# design.net
KiCad netlist of a schematic drawn in Altium Designer
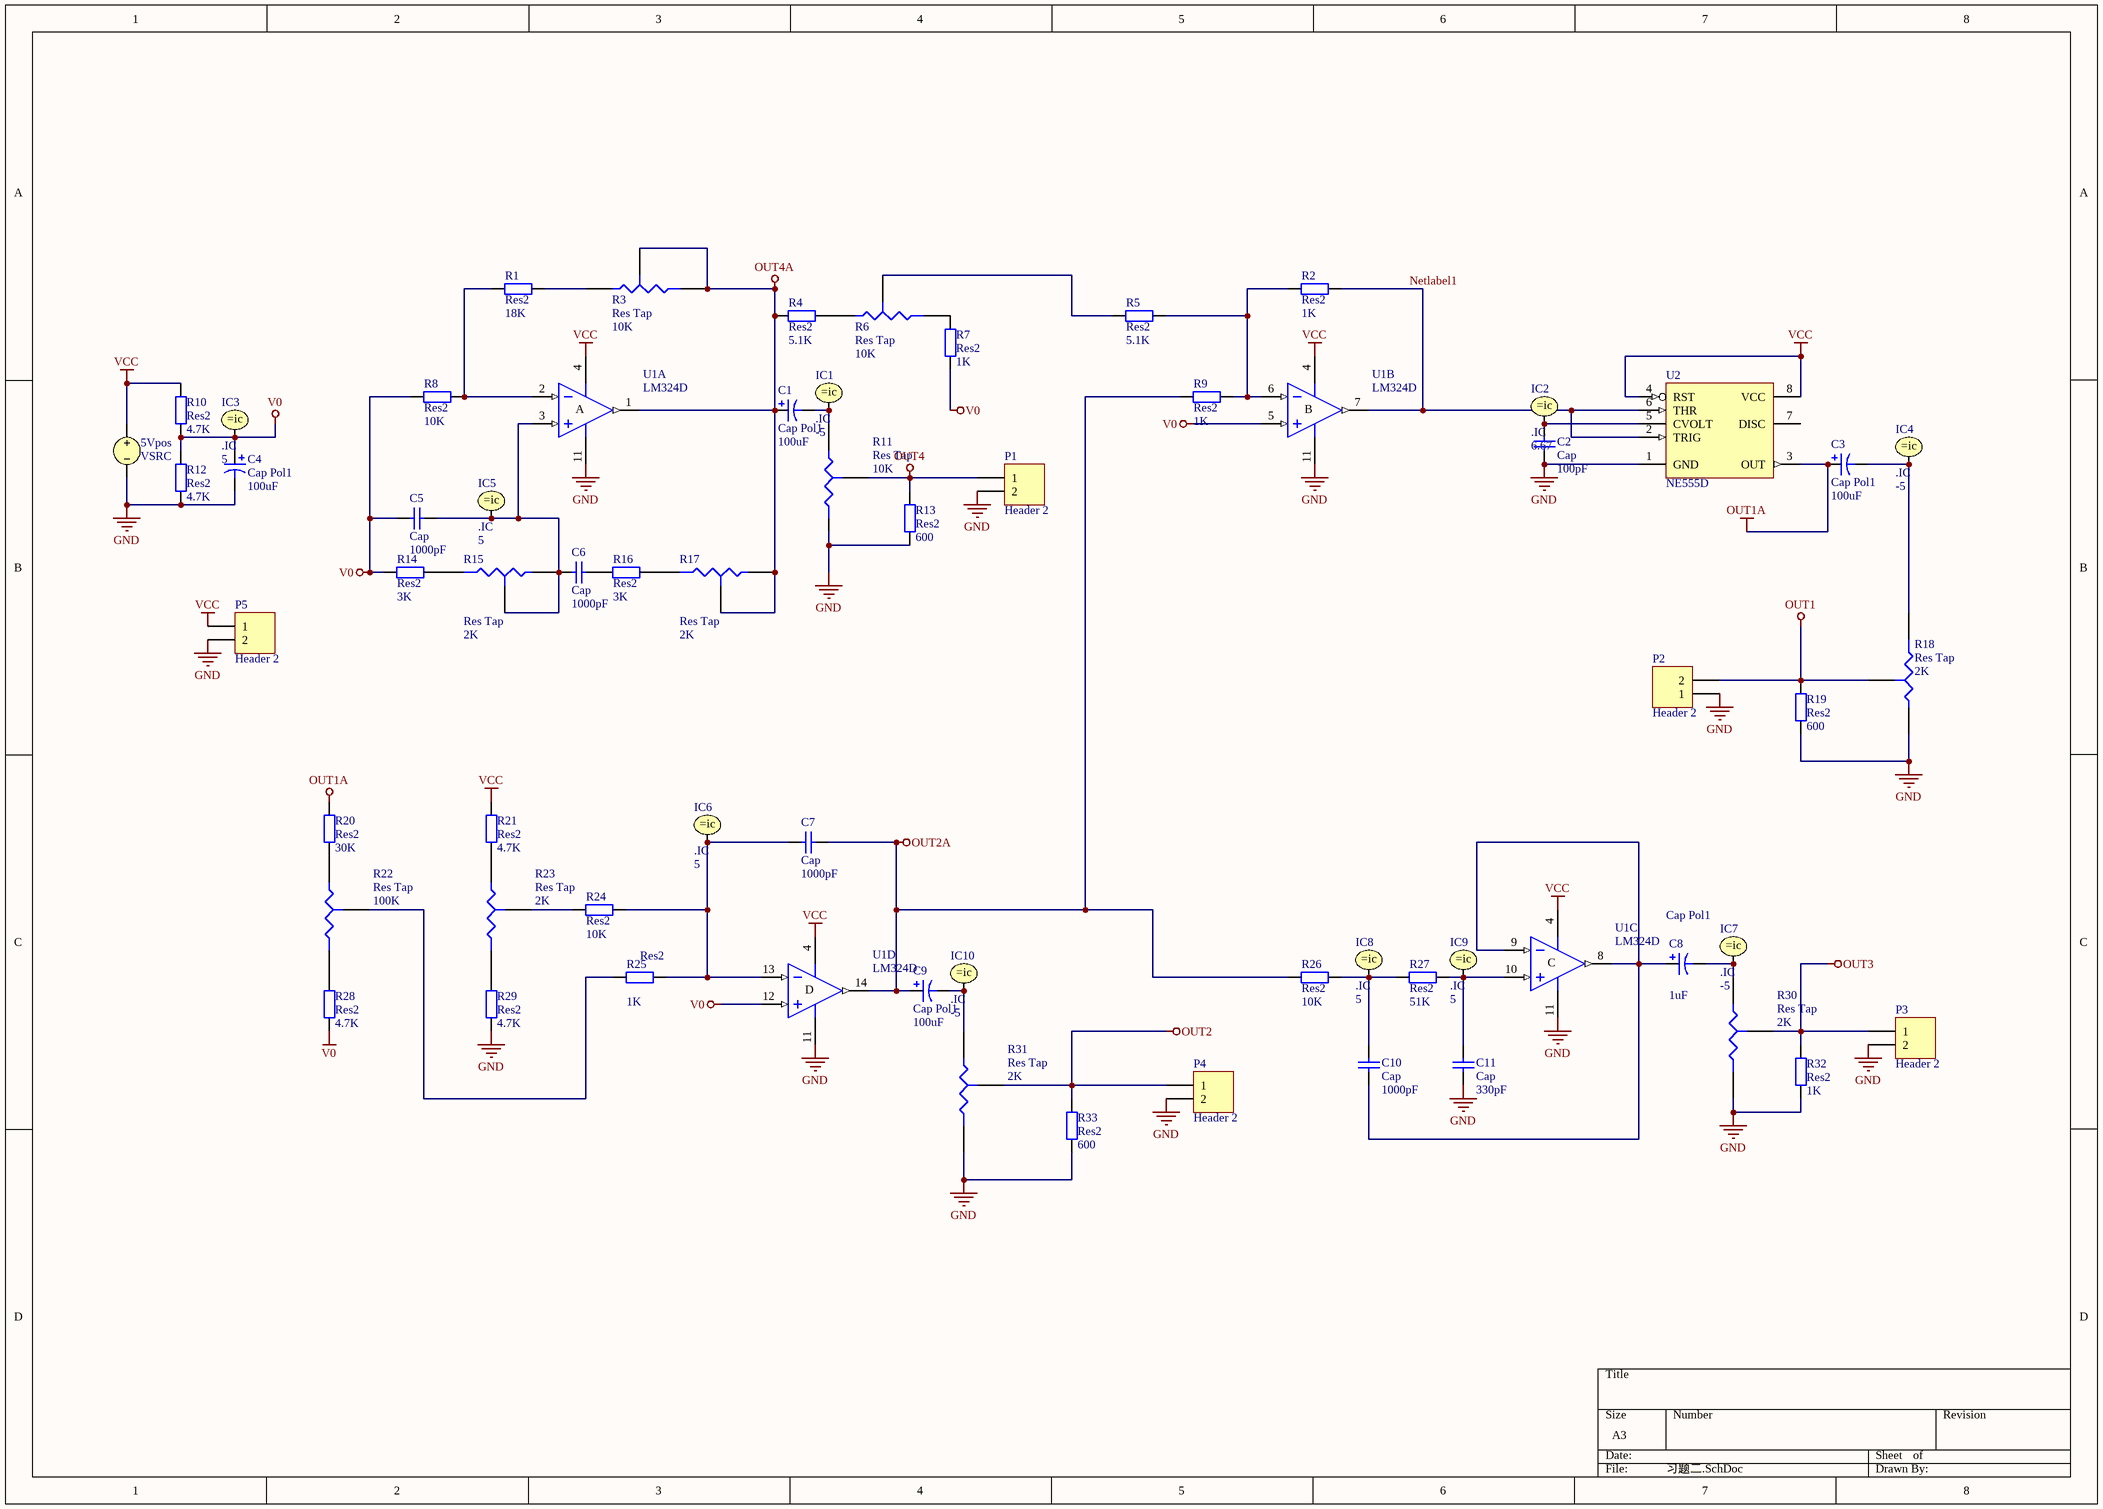
[diagram p0: 习题二.SchDoc]

(export (version "E")
  (design (tool "Eeschema 10.0.6"))
  (components
    (comp (ref "5Vpos")
      (value "VSRC")
      (footprint "PIN1")
      (description "Voltage Source")
      (fields (field (name "PUBLISHER") "Altium Limited"))
      (libsource (lib "Simulation Sources") (part "VSRC"))
    )
    (comp (ref "C1")
      (value "Cap Pol1")
      (footprint "LC-CASE-C_6032")
      (description "Polarized Capacitor (Radial)")
      (fields (field (name "ALTIUM_VALUE") "100uF") (field (name "PUBLISHER") "Altium Limited"))
      (libsource (lib "Miscellaneous Devices") (part "Cap Pol1"))
    )
    (comp (ref "C2")
      (value "Cap")
      (footprint "LC-0805_C")
      (description "Capacitor")
      (fields (field (name "ALTIUM_VALUE") "100pF") (field (name "PUBLISHER") "Altium Limited"))
      (libsource (lib "Miscellaneous Devices") (part "Cap"))
    )
    (comp (ref "C3")
      (value "Cap Pol1")
      (footprint "LC-CASE-C_6032")
      (description "Polarized Capacitor (Radial)")
      (fields (field (name "ALTIUM_VALUE") "100uF") (field (name "PUBLISHER") "Altium Limited"))
      (libsource (lib "Miscellaneous Devices") (part "Cap Pol1"))
    )
    (comp (ref "C4")
      (value "Cap Pol1")
      (footprint "C-RB-5.0/10")
      (description "Polarized Capacitor (Radial)")
      (fields (field (name "ALTIUM_VALUE") "100uF") (field (name "PUBLISHER") "Altium Limited"))
      (libsource (lib "Miscellaneous Devices") (part "Cap Pol1"))
    )
    (comp (ref "C5")
      (value "Cap")
      (footprint "LC-0805_C")
      (description "Capacitor")
      (fields (field (name "ALTIUM_VALUE") "1000pF") (field (name "PUBLISHER") "Altium Limited"))
      (libsource (lib "Miscellaneous Devices") (part "Cap"))
    )
    (comp (ref "C6")
      (value "Cap")
      (footprint "LC-0805_C")
      (description "Capacitor")
      (fields (field (name "ALTIUM_VALUE") "1000pF") (field (name "PUBLISHER") "Altium Limited"))
      (libsource (lib "Miscellaneous Devices") (part "Cap"))
    )
    (comp (ref "C7")
      (value "Cap")
      (footprint "LC-0805_C")
      (description "Capacitor")
      (fields (field (name "ALTIUM_VALUE") "1000pF") (field (name "PUBLISHER") "Altium Limited"))
      (libsource (lib "Miscellaneous Devices") (part "Cap"))
    )
    (comp (ref "C8")
      (value "Cap Pol1")
      (footprint "LC-CASE-C_6032")
      (description "Polarized Capacitor (Radial)")
      (fields (field (name "ALTIUM_VALUE") "1uF") (field (name "PUBLISHER") "Altium Limited"))
      (libsource (lib "Miscellaneous Devices") (part "Cap Pol1"))
    )
    (comp (ref "C9")
      (value "Cap Pol1")
      (footprint "LC-CASE-C_6032")
      (description "Polarized Capacitor (Radial)")
      (fields (field (name "ALTIUM_VALUE") "100uF") (field (name "PUBLISHER") "Altium Limited"))
      (libsource (lib "Miscellaneous Devices") (part "Cap Pol1"))
    )
    (comp (ref "C10")
      (value "Cap")
      (footprint "LC-0805_C")
      (description "Capacitor")
      (fields (field (name "ALTIUM_VALUE") "1000pF") (field (name "PUBLISHER") "Altium Limited"))
      (libsource (lib "Miscellaneous Devices") (part "Cap"))
    )
    (comp (ref "C11")
      (value "Cap")
      (footprint "LC-0805_C")
      (description "Capacitor")
      (fields (field (name "ALTIUM_VALUE") "330pF") (field (name "PUBLISHER") "Altium Limited"))
      (libsource (lib "Miscellaneous Devices") (part "Cap"))
    )
    (comp (ref "IC1")
      (value ".IC")
      (description "Initial Condition")
      (fields (field (name "INITIAL VOLTAGE") "-5") (field (name "PUBLISHER") "Altium Limited"))
      (libsource (lib "Simulation Sources") (part ".IC"))
    )
    (comp (ref "IC2")
      (value ".IC")
      (description "Initial Condition")
      (fields (field (name "INITIAL VOLTAGE") "6.67") (field (name "PUBLISHER") "Altium Limited"))
      (libsource (lib "Simulation Sources") (part ".IC"))
    )
    (comp (ref "IC3")
      (value ".IC")
      (description "Initial Condition")
      (fields (field (name "INITIAL VOLTAGE") "5") (field (name "PUBLISHER") "Altium Limited"))
      (libsource (lib "Simulation Sources") (part ".IC"))
    )
    (comp (ref "IC4")
      (value ".IC")
      (description "Initial Condition")
      (fields (field (name "INITIAL VOLTAGE") "-5") (field (name "PUBLISHER") "Altium Limited"))
      (libsource (lib "Simulation Sources") (part ".IC"))
    )
    (comp (ref "IC5")
      (value ".IC")
      (description "Initial Condition")
      (fields (field (name "INITIAL VOLTAGE") "5") (field (name "PUBLISHER") "Altium Limited"))
      (libsource (lib "Simulation Sources") (part ".IC"))
    )
    (comp (ref "IC6")
      (value ".IC")
      (description "Initial Condition")
      (fields (field (name "INITIAL VOLTAGE") "5") (field (name "PUBLISHER") "Altium Limited"))
      (libsource (lib "Simulation Sources") (part ".IC"))
    )
    (comp (ref "IC7")
      (value ".IC")
      (description "Initial Condition")
      (fields (field (name "INITIAL VOLTAGE") "-5") (field (name "PUBLISHER") "Altium Limited"))
      (libsource (lib "Simulation Sources") (part ".IC"))
    )
    (comp (ref "IC8")
      (value ".IC")
      (description "Initial Condition")
      (fields (field (name "INITIAL VOLTAGE") "5") (field (name "PUBLISHER") "Altium Limited"))
      (libsource (lib "Simulation Sources") (part ".IC"))
    )
    (comp (ref "IC9")
      (value ".IC")
      (description "Initial Condition")
      (fields (field (name "INITIAL VOLTAGE") "5") (field (name "PUBLISHER") "Altium Limited"))
      (libsource (lib "Simulation Sources") (part ".IC"))
    )
    (comp (ref "IC10")
      (value ".IC")
      (description "Initial Condition")
      (fields (field (name "INITIAL VOLTAGE") "-5") (field (name "PUBLISHER") "Altium Limited"))
      (libsource (lib "Simulation Sources") (part ".IC"))
    )
    (comp (ref "P1")
      (value "Header 2")
      (footprint "HDR1X2")
      (description "Header, 2-Pin")
      (fields (field (name "PUBLISHER") "Altium Limited"))
      (libsource (lib "Miscellaneous Connectors") (part "Header 2"))
    )
    (comp (ref "P2")
      (value "Header 2")
      (footprint "HDR1X2")
      (description "Header, 2-Pin")
      (fields (field (name "PUBLISHER") "Altium Limited"))
      (libsource (lib "") (part "Header 2_1"))
    )
    (comp (ref "P3")
      (value "Header 2")
      (footprint "HDR1X2")
      (description "Header, 2-Pin")
      (fields (field (name "PUBLISHER") "Altium Limited"))
      (libsource (lib "Miscellaneous Connectors") (part "Header 2"))
    )
    (comp (ref "P4")
      (value "Header 2")
      (footprint "HDR1X2")
      (description "Header, 2-Pin")
      (fields (field (name "PUBLISHER") "Altium Limited"))
      (libsource (lib "Miscellaneous Connectors") (part "Header 2"))
    )
    (comp (ref "P5")
      (value "Header 2")
      (footprint "HDR1X2")
      (description "Header, 2-Pin")
      (fields (field (name "PUBLISHER") "Altium Limited"))
      (libsource (lib "Miscellaneous Connectors") (part "Header 2"))
    )
    (comp (ref "R1")
      (value "Res2")
      (footprint "LC-0805_R")
      (description "Resistor")
      (fields (field (name "ALTIUM_VALUE") "18K") (field (name "PUBLISHER") "Altium Limited"))
      (libsource (lib "Miscellaneous Devices") (part "Res2"))
    )
    (comp (ref "R2")
      (value "Res2")
      (footprint "LC-0805_R")
      (description "Resistor")
      (fields (field (name "ALTIUM_VALUE") "1K") (field (name "PUBLISHER") "Altium Limited"))
      (libsource (lib "Miscellaneous Devices") (part "Res2"))
    )
    (comp (ref "R3")
      (value "Res Tap")
      (footprint "电位器")
      (description "Tapped Resistor")
      (fields (field (name "ALTIUM_VALUE") "10K") (field (name "PUBLISHER") "Altium Limited"))
      (libsource (lib "Miscellaneous Devices") (part "Res Tap"))
    )
    (comp (ref "R4")
      (value "Res2")
      (footprint "LC-0805_R")
      (description "Resistor")
      (fields (field (name "ALTIUM_VALUE") "5.1K") (field (name "PUBLISHER") "Altium Limited"))
      (libsource (lib "Miscellaneous Devices") (part "Res2"))
    )
    (comp (ref "R5")
      (value "Res2")
      (footprint "LC-0805_R")
      (description "Resistor")
      (fields (field (name "ALTIUM_VALUE") "5.1K") (field (name "PUBLISHER") "Altium Limited"))
      (libsource (lib "Miscellaneous Devices") (part "Res2"))
    )
    (comp (ref "R6")
      (value "Res Tap")
      (footprint "电位器")
      (description "Tapped Resistor")
      (fields (field (name "ALTIUM_VALUE") "10K") (field (name "PUBLISHER") "Altium Limited"))
      (libsource (lib "Miscellaneous Devices") (part "Res Tap"))
    )
    (comp (ref "R7")
      (value "Res2")
      (footprint "LC-0805_R")
      (description "Resistor")
      (fields (field (name "ALTIUM_VALUE") "1K") (field (name "PUBLISHER") "Altium Limited"))
      (libsource (lib "") (part "Res2_1"))
    )
    (comp (ref "R8")
      (value "Res2")
      (footprint "LC-0805_R")
      (description "Resistor")
      (fields (field (name "ALTIUM_VALUE") "10K") (field (name "PUBLISHER") "Altium Limited"))
      (libsource (lib "Miscellaneous Devices") (part "Res2"))
    )
    (comp (ref "R9")
      (value "Res2")
      (footprint "LC-0805_R")
      (description "Resistor")
      (fields (field (name "ALTIUM_VALUE") "1K") (field (name "PUBLISHER") "Altium Limited"))
      (libsource (lib "Miscellaneous Devices") (part "Res2"))
    )
    (comp (ref "R10")
      (value "Res2")
      (footprint "LC-0805_R")
      (description "Resistor")
      (fields (field (name "ALTIUM_VALUE") "4.7K") (field (name "PUBLISHER") "Altium Limited"))
      (libsource (lib "") (part "Res2_1"))
    )
    (comp (ref "R11")
      (value "Res Tap")
      (footprint "电位器")
      (description "Tapped Resistor")
      (fields (field (name "ALTIUM_VALUE") "10K") (field (name "PUBLISHER") "Altium Limited"))
      (libsource (lib "Miscellaneous Devices") (part "Res Tap"))
    )
    (comp (ref "R12")
      (value "Res2")
      (footprint "LC-0805_R")
      (description "Resistor")
      (fields (field (name "ALTIUM_VALUE") "4.7K") (field (name "PUBLISHER") "Altium Limited"))
      (libsource (lib "") (part "Res2_1"))
    )
    (comp (ref "R13")
      (value "Res2")
      (footprint "LC-0805_R")
      (description "Resistor")
      (fields (field (name "ALTIUM_VALUE") "600") (field (name "PUBLISHER") "Altium Limited"))
      (libsource (lib "") (part "Res2_1"))
    )
    (comp (ref "R14")
      (value "Res2")
      (footprint "LC-0805_R")
      (description "Resistor")
      (fields (field (name "ALTIUM_VALUE") "3K") (field (name "PUBLISHER") "Altium Limited"))
      (libsource (lib "Miscellaneous Devices") (part "Res2"))
    )
    (comp (ref "R15")
      (value "Res Tap")
      (footprint "电位器")
      (description "Tapped Resistor")
      (fields (field (name "ALTIUM_VALUE") "2K") (field (name "PUBLISHER") "Altium Limited"))
      (libsource (lib "Miscellaneous Devices") (part "Res Tap"))
    )
    (comp (ref "R16")
      (value "Res2")
      (footprint "LC-0805_R")
      (description "Resistor")
      (fields (field (name "ALTIUM_VALUE") "3K") (field (name "PUBLISHER") "Altium Limited"))
      (libsource (lib "Miscellaneous Devices") (part "Res2"))
    )
    (comp (ref "R17")
      (value "Res Tap")
      (footprint "电位器")
      (description "Tapped Resistor")
      (fields (field (name "ALTIUM_VALUE") "2K") (field (name "PUBLISHER") "Altium Limited"))
      (libsource (lib "Miscellaneous Devices") (part "Res Tap"))
    )
    (comp (ref "R18")
      (value "Res Tap")
      (footprint "电位器")
      (description "Tapped Resistor")
      (fields (field (name "ALTIUM_VALUE") "2K") (field (name "PUBLISHER") "Altium Limited"))
      (libsource (lib "Miscellaneous Devices") (part "Res Tap"))
    )
    (comp (ref "R19")
      (value "Res2")
      (footprint "LC-0805_R")
      (description "Resistor")
      (fields (field (name "ALTIUM_VALUE") "600") (field (name "PUBLISHER") "Altium Limited"))
      (libsource (lib "") (part "Res2_1"))
    )
    (comp (ref "R20")
      (value "Res2")
      (footprint "LC-0805_R")
      (description "Resistor")
      (fields (field (name "ALTIUM_VALUE") "30K") (field (name "PUBLISHER") "Altium Limited"))
      (libsource (lib "") (part "Res2_1"))
    )
    (comp (ref "R21")
      (value "Res2")
      (footprint "LC-0805_R")
      (description "Resistor")
      (fields (field (name "ALTIUM_VALUE") "4.7K") (field (name "PUBLISHER") "Altium Limited"))
      (libsource (lib "") (part "Res2_1"))
    )
    (comp (ref "R22")
      (value "Res Tap")
      (footprint "电位器")
      (description "Tapped Resistor")
      (fields (field (name "ALTIUM_VALUE") "100K") (field (name "PUBLISHER") "Altium Limited"))
      (libsource (lib "Miscellaneous Devices") (part "Res Tap"))
    )
    (comp (ref "R23")
      (value "Res Tap")
      (footprint "电位器")
      (description "Tapped Resistor")
      (fields (field (name "ALTIUM_VALUE") "2K") (field (name "PUBLISHER") "Altium Limited"))
      (libsource (lib "Miscellaneous Devices") (part "Res Tap"))
    )
    (comp (ref "R24")
      (value "Res2")
      (footprint "LC-0805_R")
      (description "Resistor")
      (fields (field (name "ALTIUM_VALUE") "10K") (field (name "PUBLISHER") "Altium Limited"))
      (libsource (lib "Miscellaneous Devices") (part "Res2"))
    )
    (comp (ref "R25")
      (value "Res2")
      (footprint "LC-0805_R")
      (description "Resistor")
      (fields (field (name "ALTIUM_VALUE") "1K") (field (name "PUBLISHER") "Altium Limited"))
      (libsource (lib "Miscellaneous Devices") (part "Res2"))
    )
    (comp (ref "R26")
      (value "Res2")
      (footprint "LC-0805_R")
      (description "Resistor")
      (fields (field (name "ALTIUM_VALUE") "10K") (field (name "PUBLISHER") "Altium Limited"))
      (libsource (lib "Miscellaneous Devices") (part "Res2"))
    )
    (comp (ref "R27")
      (value "Res2")
      (footprint "LC-0805_R")
      (description "Resistor")
      (fields (field (name "ALTIUM_VALUE") "51K") (field (name "PUBLISHER") "Altium Limited"))
      (libsource (lib "Miscellaneous Devices") (part "Res2"))
    )
    (comp (ref "R28")
      (value "Res2")
      (footprint "LC-0805_R")
      (description "Resistor")
      (fields (field (name "ALTIUM_VALUE") "4.7K") (field (name "PUBLISHER") "Altium Limited"))
      (libsource (lib "") (part "Res2_1"))
    )
    (comp (ref "R29")
      (value "Res2")
      (footprint "LC-0805_R")
      (description "Resistor")
      (fields (field (name "ALTIUM_VALUE") "4.7K") (field (name "PUBLISHER") "Altium Limited"))
      (libsource (lib "") (part "Res2_1"))
    )
    (comp (ref "R30")
      (value "Res Tap")
      (footprint "电位器")
      (description "Tapped Resistor")
      (fields (field (name "ALTIUM_VALUE") "2K") (field (name "PUBLISHER") "Altium Limited"))
      (libsource (lib "Miscellaneous Devices") (part "Res Tap"))
    )
    (comp (ref "R31")
      (value "Res Tap")
      (footprint "电位器")
      (description "Tapped Resistor")
      (fields (field (name "ALTIUM_VALUE") "2K") (field (name "PUBLISHER") "Altium Limited"))
      (libsource (lib "Miscellaneous Devices") (part "Res Tap"))
    )
    (comp (ref "R32")
      (value "Res2")
      (footprint "LC-0805_R")
      (description "Resistor")
      (fields (field (name "ALTIUM_VALUE") "1K") (field (name "PUBLISHER") "Altium Limited"))
      (libsource (lib "") (part "Res2_1"))
    )
    (comp (ref "R33")
      (value "Res2")
      (footprint "LC-0805_R")
      (description "Resistor")
      (fields (field (name "ALTIUM_VALUE") "600") (field (name "PUBLISHER") "Altium Limited"))
      (libsource (lib "") (part "Res2_1"))
    )
    (comp (ref "U1")
      (value "LM324D")
      (footprint "SO14_N")
      (description "Low-Power Quad Operational Amplifier")
      (fields (field (name "PUBLISHER") "Altium Limited"))
      (libsource (lib "ST Operational Amplifier") (part "LM324D"))
    )
    (comp (ref "U2")
      (value "NE555D")
      (footprint "D008_N")
      (description "Precision Timer")
      (fields (field (name "PUBLISHER") "Altium Limited"))
      (libsource (lib "TI Analog Timer Circuit") (part "NE555D"))
    )
  )
  (nets
    (net (code "1") (name "/Netlabel1") (class "Default")
      (node (ref "R2") (pin "2") (pinfunction "2_2") (pintype "passive"))
      (node (ref "U1") (pin "7") (pinfunction "OUT_7") (pintype "output"))
      (node (ref "U2") (pin "2") (pinfunction "TRIG_2") (pintype "input"))
      (node (ref "U2") (pin "6") (pinfunction "THR_6") (pintype "input"))
    )
    (net (code "2") (name "GND") (class "Default")
      (node (ref "5Vpos") (pin "2") (pinfunction "2_2") (pintype "passive"))
      (node (ref "C11") (pin "1") (pinfunction "1_1") (pintype "passive"))
      (node (ref "C2") (pin "1") (pinfunction "1_1") (pintype "passive"))
      (node (ref "C4") (pin "2") (pinfunction "2_2") (pintype "passive"))
      (node (ref "P1") (pin "2") (pinfunction "2_2") (pintype "passive"))
      (node (ref "P2") (pin "1") (pinfunction "1_1") (pintype "passive"))
      (node (ref "P3") (pin "2") (pinfunction "2_2") (pintype "passive"))
      (node (ref "P4") (pin "2") (pinfunction "2_2") (pintype "passive"))
      (node (ref "P5") (pin "2") (pinfunction "2_2") (pintype "passive"))
      (node (ref "R11") (pin "2") (pinfunction "B_2") (pintype "passive"))
      (node (ref "R12") (pin "1") (pinfunction "1_1") (pintype "passive"))
      (node (ref "R13") (pin "1") (pinfunction "1_1") (pintype "passive"))
      (node (ref "R18") (pin "1") (pinfunction "A_1") (pintype "passive"))
      (node (ref "R19") (pin "1") (pinfunction "1_1") (pintype "passive"))
      (node (ref "R29") (pin "1") (pinfunction "1_1") (pintype "passive"))
      (node (ref "R30") (pin "2") (pinfunction "B_2") (pintype "passive"))
      (node (ref "R31") (pin "2") (pinfunction "B_2") (pintype "passive"))
      (node (ref "R32") (pin "1") (pinfunction "1_1") (pintype "passive"))
      (node (ref "R33") (pin "1") (pinfunction "1_1") (pintype "passive"))
      (node (ref "U1") (pin "11") (pinfunction "V-_11") (pintype "power_in"))
      (node (ref "U2") (pin "1") (pinfunction "GND_1") (pintype "power_in"))
    )
    (net (code "3") (name "Net-(C6-Pad2)") (class "Default")
      (node (ref "C6") (pin "2") (pinfunction "2_2") (pintype "passive"))
      (node (ref "R16") (pin "1") (pinfunction "1_1") (pintype "passive"))
    )
    (net (code "4") (name "Net-(C10-Pad2)") (class "Default")
      (node (ref "C10") (pin "2") (pinfunction "2_2") (pintype "passive"))
      (node (ref "IC8") (pin "1") (pinfunction "1_1") (pintype "passive"))
      (node (ref "R26") (pin "2") (pinfunction "2_2") (pintype "passive"))
      (node (ref "R27") (pin "1") (pinfunction "1_1") (pintype "passive"))
    )
    (net (code "5") (name "Net-(R3-A)") (class "Default")
      (node (ref "R1") (pin "2") (pinfunction "2_2") (pintype "passive"))
      (node (ref "R3") (pin "1") (pinfunction "A_1") (pintype "passive"))
    )
    (net (code "6") (name "Net-(R6-A)") (class "Default")
      (node (ref "R4") (pin "2") (pinfunction "2_2") (pintype "passive"))
      (node (ref "R6") (pin "1") (pinfunction "A_1") (pintype "passive"))
    )
    (net (code "7") (name "Net-(R6-B)") (class "Default")
      (node (ref "R6") (pin "2") (pinfunction "B_2") (pintype "passive"))
      (node (ref "R7") (pin "2") (pinfunction "2_2") (pintype "passive"))
    )
    (net (code "8") (name "Net-(R6-TAP)") (class "Default")
      (node (ref "R5") (pin "1") (pinfunction "1_1") (pintype "passive"))
      (node (ref "R6") (pin "3") (pinfunction "TAP_3") (pintype "passive"))
    )
    (net (code "9") (name "Net-(R11-A)") (class "Default")
      (node (ref "C1") (pin "2") (pinfunction "2_2") (pintype "passive"))
      (node (ref "IC1") (pin "1") (pinfunction "1_1") (pintype "passive"))
      (node (ref "R11") (pin "1") (pinfunction "A_1") (pintype "passive"))
    )
    (net (code "10") (name "Net-(R15-A)") (class "Default")
      (node (ref "C5") (pin "2") (pinfunction "2_2") (pintype "passive"))
      (node (ref "C6") (pin "1") (pinfunction "1_1") (pintype "passive"))
      (node (ref "IC5") (pin "1") (pinfunction "1_1") (pintype "passive"))
      (node (ref "R15") (pin "1") (pinfunction "A_1") (pintype "passive"))
      (node (ref "R15") (pin "3") (pinfunction "TAP_3") (pintype "passive"))
      (node (ref "U1") (pin "3") (pinfunction "IN+_3") (pintype "input"))
    )
    (net (code "11") (name "Net-(R15-B)") (class "Default")
      (node (ref "R14") (pin "2") (pinfunction "2_2") (pintype "passive"))
      (node (ref "R15") (pin "2") (pinfunction "B_2") (pintype "passive"))
    )
    (net (code "12") (name "Net-(R17-B)") (class "Default")
      (node (ref "R16") (pin "2") (pinfunction "2_2") (pintype "passive"))
      (node (ref "R17") (pin "2") (pinfunction "B_2") (pintype "passive"))
    )
    (net (code "13") (name "Net-(R18-B)") (class "Default")
      (node (ref "C3") (pin "2") (pinfunction "2_2") (pintype "passive"))
      (node (ref "IC4") (pin "1") (pinfunction "1_1") (pintype "passive"))
      (node (ref "R18") (pin "2") (pinfunction "B_2") (pintype "passive"))
    )
    (net (code "14") (name "Net-(R22-A)") (class "Default")
      (node (ref "R20") (pin "1") (pinfunction "1_1") (pintype "passive"))
      (node (ref "R22") (pin "1") (pinfunction "A_1") (pintype "passive"))
    )
    (net (code "15") (name "Net-(R22-B)") (class "Default")
      (node (ref "R22") (pin "2") (pinfunction "B_2") (pintype "passive"))
      (node (ref "R28") (pin "2") (pinfunction "2_2") (pintype "passive"))
    )
    (net (code "16") (name "Net-(R22-TAP)") (class "Default")
      (node (ref "R22") (pin "3") (pinfunction "TAP_3") (pintype "passive"))
      (node (ref "R25") (pin "1") (pinfunction "1_1") (pintype "passive"))
    )
    (net (code "17") (name "Net-(R23-A)") (class "Default")
      (node (ref "R21") (pin "1") (pinfunction "1_1") (pintype "passive"))
      (node (ref "R23") (pin "1") (pinfunction "A_1") (pintype "passive"))
    )
    (net (code "18") (name "Net-(R23-B)") (class "Default")
      (node (ref "R23") (pin "2") (pinfunction "B_2") (pintype "passive"))
      (node (ref "R29") (pin "2") (pinfunction "2_2") (pintype "passive"))
    )
    (net (code "19") (name "Net-(R23-TAP)") (class "Default")
      (node (ref "R23") (pin "3") (pinfunction "TAP_3") (pintype "passive"))
      (node (ref "R24") (pin "1") (pinfunction "1_1") (pintype "passive"))
    )
    (net (code "20") (name "Net-(R30-A)") (class "Default")
      (node (ref "C8") (pin "2") (pinfunction "2_2") (pintype "passive"))
      (node (ref "IC7") (pin "1") (pinfunction "1_1") (pintype "passive"))
      (node (ref "R30") (pin "1") (pinfunction "A_1") (pintype "passive"))
    )
    (net (code "21") (name "Net-(R31-A)") (class "Default")
      (node (ref "C9") (pin "2") (pinfunction "2_2") (pintype "passive"))
      (node (ref "IC10") (pin "1") (pinfunction "1_1") (pintype "passive"))
      (node (ref "R31") (pin "1") (pinfunction "A_1") (pintype "passive"))
    )
    (net (code "22") (name "Net-(U1A-IN-)") (class "Default")
      (node (ref "R1") (pin "1") (pinfunction "1_1") (pintype "passive"))
      (node (ref "R8") (pin "2") (pinfunction "2_2") (pintype "passive"))
      (node (ref "U1") (pin "2") (pinfunction "IN-_2") (pintype "input"))
    )
    (net (code "23") (name "Net-(U1B-IN-)") (class "Default")
      (node (ref "R2") (pin "1") (pinfunction "1_1") (pintype "passive"))
      (node (ref "R5") (pin "2") (pinfunction "2_2") (pintype "passive"))
      (node (ref "R9") (pin "2") (pinfunction "2_2") (pintype "passive"))
      (node (ref "U1") (pin "6") (pinfunction "IN-_6") (pintype "input"))
    )
    (net (code "24") (name "Net-(U1C-IN+)") (class "Default")
      (node (ref "C11") (pin "2") (pinfunction "2_2") (pintype "passive"))
      (node (ref "IC9") (pin "1") (pinfunction "1_1") (pintype "passive"))
      (node (ref "R27") (pin "2") (pinfunction "2_2") (pintype "passive"))
      (node (ref "U1") (pin "10") (pinfunction "IN+_10") (pintype "input"))
    )
    (net (code "25") (name "Net-(U1C-IN-)") (class "Default")
      (node (ref "C10") (pin "1") (pinfunction "1_1") (pintype "passive"))
      (node (ref "C8") (pin "1") (pinfunction "1_1") (pintype "passive"))
      (node (ref "U1") (pin "8") (pinfunction "OUT_8") (pintype "output"))
      (node (ref "U1") (pin "9") (pinfunction "IN-_9") (pintype "input"))
    )
    (net (code "26") (name "Net-(U1D-IN-)") (class "Default")
      (node (ref "C7") (pin "1") (pinfunction "1_1") (pintype "passive"))
      (node (ref "IC6") (pin "1") (pinfunction "1_1") (pintype "passive"))
      (node (ref "R24") (pin "2") (pinfunction "2_2") (pintype "passive"))
      (node (ref "R25") (pin "2") (pinfunction "2_2") (pintype "passive"))
      (node (ref "U1") (pin "13") (pinfunction "IN-_13") (pintype "input"))
    )
    (net (code "27") (name "Net-(U2-CVOLT)") (class "Default")
      (node (ref "C2") (pin "2") (pinfunction "2_2") (pintype "passive"))
      (node (ref "IC2") (pin "1") (pinfunction "1_1") (pintype "passive"))
      (node (ref "U2") (pin "5") (pinfunction "CVOLT_5") (pintype "passive"))
    )
    (net (code "28") (name "OUT1") (class "Default")
      (node (ref "P2") (pin "2") (pinfunction "2_2") (pintype "passive"))
      (node (ref "R18") (pin "3") (pinfunction "TAP_3") (pintype "passive"))
      (node (ref "R19") (pin "2") (pinfunction "2_2") (pintype "passive"))
    )
    (net (code "29") (name "OUT1A") (class "Default")
      (node (ref "C3") (pin "1") (pinfunction "1_1") (pintype "passive"))
      (node (ref "R20") (pin "2") (pinfunction "2_2") (pintype "passive"))
      (node (ref "U2") (pin "3") (pinfunction "OUT_3") (pintype "output"))
    )
    (net (code "30") (name "OUT2") (class "Default")
      (node (ref "P4") (pin "1") (pinfunction "1_1") (pintype "passive"))
      (node (ref "R31") (pin "3") (pinfunction "TAP_3") (pintype "passive"))
      (node (ref "R33") (pin "2") (pinfunction "2_2") (pintype "passive"))
    )
    (net (code "31") (name "OUT2A") (class "Default")
      (node (ref "C7") (pin "2") (pinfunction "2_2") (pintype "passive"))
      (node (ref "C9") (pin "1") (pinfunction "1_1") (pintype "passive"))
      (node (ref "R26") (pin "1") (pinfunction "1_1") (pintype "passive"))
      (node (ref "R9") (pin "1") (pinfunction "1_1") (pintype "passive"))
      (node (ref "U1") (pin "14") (pinfunction "OUT_14") (pintype "output"))
    )
    (net (code "32") (name "OUT3") (class "Default")
      (node (ref "P3") (pin "1") (pinfunction "1_1") (pintype "passive"))
      (node (ref "R30") (pin "3") (pinfunction "TAP_3") (pintype "passive"))
      (node (ref "R32") (pin "2") (pinfunction "2_2") (pintype "passive"))
    )
    (net (code "33") (name "OUT4") (class "Default")
      (node (ref "P1") (pin "1") (pinfunction "1_1") (pintype "passive"))
      (node (ref "R11") (pin "3") (pinfunction "TAP_3") (pintype "passive"))
      (node (ref "R13") (pin "2") (pinfunction "2_2") (pintype "passive"))
    )
    (net (code "34") (name "OUT4A") (class "Default")
      (node (ref "C1") (pin "1") (pinfunction "1_1") (pintype "passive"))
      (node (ref "R17") (pin "1") (pinfunction "A_1") (pintype "passive"))
      (node (ref "R17") (pin "3") (pinfunction "TAP_3") (pintype "passive"))
      (node (ref "R3") (pin "2") (pinfunction "B_2") (pintype "passive"))
      (node (ref "R3") (pin "3") (pinfunction "TAP_3") (pintype "passive"))
      (node (ref "R4") (pin "1") (pinfunction "1_1") (pintype "passive"))
      (node (ref "U1") (pin "1") (pinfunction "OUT_1") (pintype "output"))
    )
    (net (code "35") (name "V0") (class "Default")
      (node (ref "C4") (pin "1") (pinfunction "1_1") (pintype "passive"))
      (node (ref "C5") (pin "1") (pinfunction "1_1") (pintype "passive"))
      (node (ref "IC3") (pin "1") (pinfunction "1_1") (pintype "passive"))
      (node (ref "R10") (pin "1") (pinfunction "1_1") (pintype "passive"))
      (node (ref "R12") (pin "2") (pinfunction "2_2") (pintype "passive"))
      (node (ref "R14") (pin "1") (pinfunction "1_1") (pintype "passive"))
      (node (ref "R28") (pin "1") (pinfunction "1_1") (pintype "passive"))
      (node (ref "R7") (pin "1") (pinfunction "1_1") (pintype "passive"))
      (node (ref "R8") (pin "1") (pinfunction "1_1") (pintype "passive"))
      (node (ref "U1") (pin "12") (pinfunction "IN+_12") (pintype "input"))
      (node (ref "U1") (pin "5") (pinfunction "IN+_5") (pintype "input"))
    )
    (net (code "36") (name "VCC") (class "Default")
      (node (ref "5Vpos") (pin "1") (pinfunction "1_1") (pintype "passive"))
      (node (ref "P5") (pin "1") (pinfunction "1_1") (pintype "passive"))
      (node (ref "R10") (pin "2") (pinfunction "2_2") (pintype "passive"))
      (node (ref "R21") (pin "2") (pinfunction "2_2") (pintype "passive"))
      (node (ref "U1") (pin "4") (pinfunction "V+_4") (pintype "power_in"))
      (node (ref "U2") (pin "4") (pinfunction "RST_4") (pintype "input"))
      (node (ref "U2") (pin "8") (pinfunction "VCC_8") (pintype "power_in"))
    )
    (net (code "37") (name "unconnected-(U2-DISC-Pad7)") (class "Default")
      (node (ref "U2") (pin "7") (pinfunction "DISC_7") (pintype "open_collector"))
    )
  )
)
